# Laser_Tanks_Tank_Motherboard.net
KiCad netlist of a schematic drawn in EasyEDA Pro
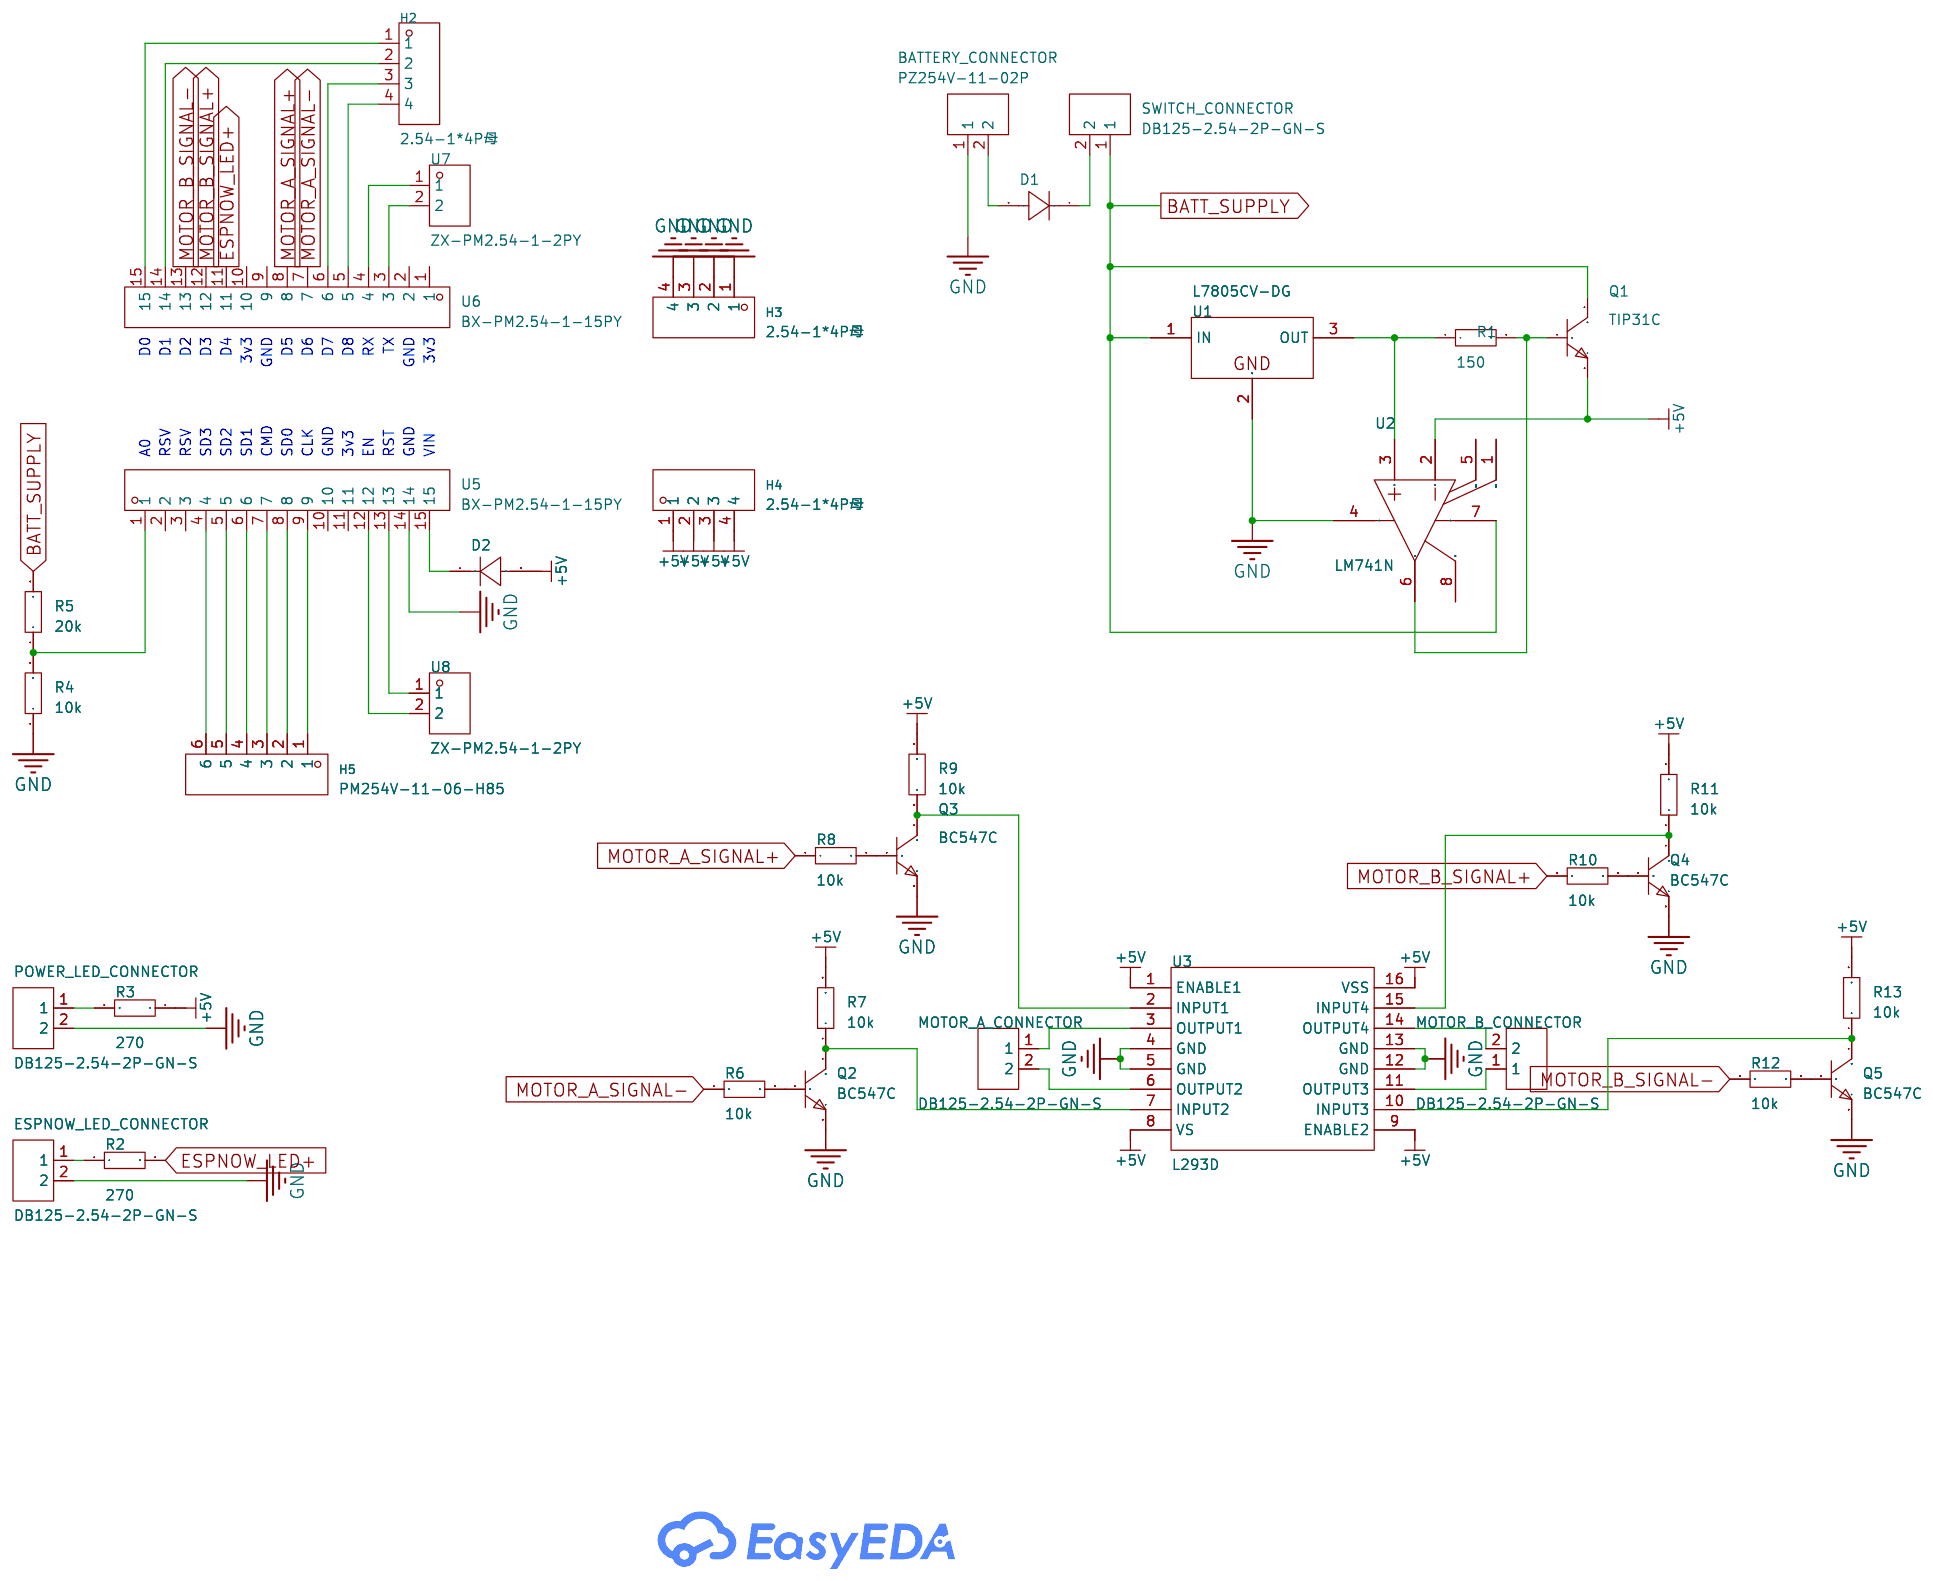
[diagram p0: schematic sheet]

(export (version "E")
  (design (tool "Eeschema 10.0.6"))
  (components
    (comp (ref "BATTERY_CONNECTOR")
      (value "PZ254V-11-02P")
      (footprint "easyedapro:HDR-TH_2P-P2.54-V-M")
      (fields (field (name "Manufacturer") "XFCN(兴飞)"))
      (libsource (lib "easyedapro") (part "PZ254V-11-02P"))
    )
    (comp (ref "D1")
      (value "~")
      (footprint "easyedapro:DO-41_BD2.4-L4.7-P8.70-D0.9-RD")
      (libsource (lib "easyedapro") (part "D_1N4007"))
    )
    (comp (ref "D2")
      (value "~")
      (footprint "easyedapro:DO-41_BD2.4-L4.7-P8.70-D0.9-RD")
      (libsource (lib "easyedapro") (part "D_1N4007"))
    )
    (comp (ref "ESPNOW_LED_CONNECTOR")
      (value "DB125-2.54-2P-GN-S")
      (footprint "easyedapro:CONN-TH_DB125-2.54-2P-GN")
      (fields (field (name "Manufacturer") "DORABO(地博电气)"))
      (libsource (lib "easyedapro") (part "DB125-2.54-2P-GN"))
    )
    (comp (ref "H2")
      (value "2.54-1*4P母")
      (footprint "easyedapro:HDR-TH_4P-P2.54-V-F")
      (fields (field (name "Manufacturer") "BOOMELE(博穆精密)"))
      (libsource (lib "easyedapro") (part "2.54-1*4P母"))
    )
    (comp (ref "H3")
      (value "2.54-1*4P母")
      (footprint "easyedapro:HDR-TH_4P-P2.54-V-F")
      (fields (field (name "Manufacturer") "BOOMELE(博穆精密)"))
      (libsource (lib "easyedapro") (part "2.54-1*4P母"))
    )
    (comp (ref "H4")
      (value "2.54-1*4P母")
      (footprint "easyedapro:HDR-TH_4P-P2.54-V-F")
      (fields (field (name "Manufacturer") "BOOMELE(博穆精密)"))
      (libsource (lib "easyedapro") (part "2.54-1*4P母"))
    )
    (comp (ref "H5")
      (value "PM254V-11-06-H85")
      (footprint "easyedapro:HDR-TH_6P-P2.54-V-F")
      (fields (field (name "Manufacturer") "XFCN(兴飞)"))
      (libsource (lib "easyedapro") (part "PM254V-11-06-H85"))
    )
    (comp (ref "MOTOR_A_CONNECTOR")
      (value "DB125-2.54-2P-GN-S")
      (footprint "easyedapro:CONN-TH_DB125-2.54-2P-GN")
      (fields (field (name "Manufacturer") "DORABO(地博电气)"))
      (libsource (lib "easyedapro") (part "DB125-2.54-2P-GN"))
    )
    (comp (ref "MOTOR_B_CONNECTOR")
      (value "DB125-2.54-2P-GN-S")
      (footprint "easyedapro:CONN-TH_DB125-2.54-2P-GN")
      (fields (field (name "Manufacturer") "DORABO(地博电气)"))
      (libsource (lib "easyedapro") (part "DB125-2.54-2P-GN"))
    )
    (comp (ref "POWER_LED_CONNECTOR")
      (value "DB125-2.54-2P-GN-S")
      (footprint "easyedapro:CONN-TH_DB125-2.54-2P-GN")
      (fields (field (name "Manufacturer") "DORABO(地博电气)"))
      (libsource (lib "easyedapro") (part "DB125-2.54-2P-GN"))
    )
    (comp (ref "Q1")
      (value "TIP31C")
      (footprint "easyedapro:TO-220-3_L10.0-W4.5-P2.54-T")
      (fields (field (name "Manufacturer") "ST(意法半导体)"))
      (libsource (lib "easyedapro") (part "TIP31C"))
    )
    (comp (ref "Q2")
      (value "BC547C")
      (footprint "easyedapro:TO-92-3_L4.9-W3.7-P1.27-L")
      (fields (field (name "Manufacturer") "LGE(鲁光)"))
      (libsource (lib "easyedapro") (part "BC547C"))
    )
    (comp (ref "Q3")
      (value "BC547C")
      (footprint "easyedapro:TO-92-3_L4.9-W3.7-P1.27-L")
      (fields (field (name "Manufacturer") "LGE(鲁光)"))
      (libsource (lib "easyedapro") (part "BC547C"))
    )
    (comp (ref "Q4")
      (value "BC547C")
      (footprint "easyedapro:TO-92-3_L4.9-W3.7-P1.27-L")
      (fields (field (name "Manufacturer") "LGE(鲁光)"))
      (libsource (lib "easyedapro") (part "BC547C"))
    )
    (comp (ref "Q5")
      (value "BC547C")
      (footprint "easyedapro:TO-92-3_L4.9-W3.7-P1.27-L")
      (fields (field (name "Manufacturer") "LGE(鲁光)"))
      (libsource (lib "easyedapro") (part "BC547C"))
    )
    (comp (ref "R1")
      (value "150")
      (footprint "easyedapro:R0603")
      (fields
        (field (name "Manufacturer Part") "MF1/4W-4.7KΩ±1% T")
        (field (name "Manufacturer") "CCO(千志电子)")
      )
      (libsource (lib "easyedapro") (part "Res"))
    )
    (comp (ref "R2")
      (value "270")
      (footprint "easyedapro:R0603")
      (fields
        (field (name "Manufacturer Part") "MF1/4W-4.7KΩ±1% T")
        (field (name "Manufacturer") "CCO(千志电子)")
      )
      (libsource (lib "easyedapro") (part "Res"))
    )
    (comp (ref "R3")
      (value "270")
      (footprint "easyedapro:R0603")
      (fields
        (field (name "Manufacturer Part") "MF1/4W-4.7KΩ±1% T")
        (field (name "Manufacturer") "CCO(千志电子)")
      )
      (libsource (lib "easyedapro") (part "Res"))
    )
    (comp (ref "R4")
      (value "10k")
      (footprint "easyedapro:R0603")
      (fields
        (field (name "Manufacturer Part") "MF1/4W-4.7KΩ±1% T")
        (field (name "Manufacturer") "CCO(千志电子)")
      )
      (libsource (lib "easyedapro") (part "Res"))
    )
    (comp (ref "R5")
      (value "20k")
      (footprint "easyedapro:R0603")
      (fields
        (field (name "Manufacturer Part") "MF1/4W-4.7KΩ±1% T")
        (field (name "Manufacturer") "CCO(千志电子)")
      )
      (libsource (lib "easyedapro") (part "Res"))
    )
    (comp (ref "R6")
      (value "10k")
      (footprint "easyedapro:R0603")
      (fields
        (field (name "Manufacturer Part") "MF1/4W-4.7KΩ±1% T")
        (field (name "Manufacturer") "CCO(千志电子)")
      )
      (libsource (lib "easyedapro") (part "Res"))
    )
    (comp (ref "R7")
      (value "10k")
      (footprint "easyedapro:R0603")
      (fields
        (field (name "Manufacturer Part") "MF1/4W-4.7KΩ±1% T")
        (field (name "Manufacturer") "CCO(千志电子)")
      )
      (libsource (lib "easyedapro") (part "Res"))
    )
    (comp (ref "R8")
      (value "10k")
      (footprint "easyedapro:R0603")
      (fields
        (field (name "Manufacturer Part") "MF1/4W-4.7KΩ±1% T")
        (field (name "Manufacturer") "CCO(千志电子)")
      )
      (libsource (lib "easyedapro") (part "Res"))
    )
    (comp (ref "R9")
      (value "10k")
      (footprint "easyedapro:R0603")
      (fields
        (field (name "Manufacturer Part") "MF1/4W-4.7KΩ±1% T")
        (field (name "Manufacturer") "CCO(千志电子)")
      )
      (libsource (lib "easyedapro") (part "Res"))
    )
    (comp (ref "R10")
      (value "10k")
      (footprint "easyedapro:R0603")
      (fields
        (field (name "Manufacturer Part") "MF1/4W-4.7KΩ±1% T")
        (field (name "Manufacturer") "CCO(千志电子)")
      )
      (libsource (lib "easyedapro") (part "Res"))
    )
    (comp (ref "R11")
      (value "10k")
      (footprint "easyedapro:R0603")
      (fields
        (field (name "Manufacturer Part") "MF1/4W-4.7KΩ±1% T")
        (field (name "Manufacturer") "CCO(千志电子)")
      )
      (libsource (lib "easyedapro") (part "Res"))
    )
    (comp (ref "R12")
      (value "10k")
      (footprint "easyedapro:R0603")
      (fields
        (field (name "Manufacturer Part") "MF1/4W-4.7KΩ±1% T")
        (field (name "Manufacturer") "CCO(千志电子)")
      )
      (libsource (lib "easyedapro") (part "Res"))
    )
    (comp (ref "R13")
      (value "10k")
      (footprint "easyedapro:R0603")
      (fields
        (field (name "Manufacturer Part") "MF1/4W-4.7KΩ±1% T")
        (field (name "Manufacturer") "CCO(千志电子)")
      )
      (libsource (lib "easyedapro") (part "Res"))
    )
    (comp (ref "SWITCH_CONNECTOR")
      (value "DB125-2.54-2P-GN-S")
      (footprint "easyedapro:CONN-TH_DB125-2.54-2P-GN")
      (fields (field (name "Manufacturer") "DORABO(地博电气)"))
      (libsource (lib "easyedapro") (part "DB125-2.54-2P-GN"))
    )
    (comp (ref "U1")
      (value "L7805CV-DG")
      (footprint "easyedapro:TO-220-3_L10.0-W4.5-P2.54-L")
      (fields (field (name "Manufacturer") "ST(意法半导体)"))
      (libsource (lib "easyedapro") (part "L7805CV-DG"))
    )
    (comp (ref "U2")
      (value "LM741N")
      (footprint "easyedapro:DIP-8_L9.3-W6.4-P2.54-LS7.6-BL")
      (fields (field (name "Manufacturer") "HGSEMI(华冠)"))
      (libsource (lib "easyedapro") (part "LM741N"))
    )
    (comp (ref "U3")
      (value "L293D")
      (footprint "easyedapro:DIP-16_L20.0-W6.4-P2.54-LS7.6-BL")
      (fields (field (name "Manufacturer") "ST(意法半导体)"))
      (libsource (lib "easyedapro") (part "L293D"))
    )
    (comp (ref "U5")
      (value "BX-PM2.54-1-15PY")
      (footprint "easyedapro:HDR-TH_15P-P2.54-V-F-1")
      (fields (field (name "Manufacturer") "Bossie(博锡)"))
      (libsource (lib "easyedapro") (part "BX-PM2.54-1-15PY"))
    )
    (comp (ref "U6")
      (value "BX-PM2.54-1-15PY")
      (footprint "easyedapro:HDR-TH_15P-P2.54-V-F-1")
      (fields (field (name "Manufacturer") "Bossie(博锡)"))
      (libsource (lib "easyedapro") (part "BX-PM2.54-1-15PY"))
    )
    (comp (ref "U7")
      (value "ZX-PM2.54-1-2PY")
      (footprint "easyedapro:HDR-TH_2P-P2.54-V-F")
      (fields (field (name "Manufacturer") "Megastar(兆星)"))
      (libsource (lib "easyedapro") (part "ZX-PM2.54-1-2PY"))
    )
    (comp (ref "U8")
      (value "ZX-PM2.54-1-2PY")
      (footprint "easyedapro:HDR-TH_2P-P2.54-V-F")
      (fields (field (name "Manufacturer") "Megastar(兆星)"))
      (libsource (lib "easyedapro") (part "ZX-PM2.54-1-2PY"))
    )
  )
  (nets
    (net (code "1") (name "+5V") (class "Default")
      (node (ref "D2") (pin "2") (pinfunction "A_2") (pintype "input"))
      (node (ref "H4") (pin "1") (pinfunction "1_1") (pintype "input"))
      (node (ref "H4") (pin "2") (pinfunction "2_2") (pintype "input"))
      (node (ref "H4") (pin "3") (pinfunction "3_3") (pintype "input"))
      (node (ref "H4") (pin "4") (pinfunction "4_4") (pintype "input"))
      (node (ref "Q1") (pin "3") (pinfunction "E_3") (pintype "unspecified"))
      (node (ref "R11") (pin "2") (pinfunction "2_2") (pintype "input"))
      (node (ref "R13") (pin "2") (pinfunction "2_2") (pintype "input"))
      (node (ref "R3") (pin "1") (pinfunction "1_1") (pintype "input"))
      (node (ref "R7") (pin "2") (pinfunction "2_2") (pintype "input"))
      (node (ref "R9") (pin "2") (pinfunction "2_2") (pintype "input"))
      (node (ref "U2") (pin "2") (pinfunction "-IN_2") (pintype "unspecified"))
      (node (ref "U3") (pin "1") (pinfunction "ENABLE1_1") (pintype "unspecified"))
      (node (ref "U3") (pin "16") (pinfunction "VSS_16") (pintype "unspecified"))
      (node (ref "U3") (pin "8") (pinfunction "VS_8") (pintype "unspecified"))
      (node (ref "U3") (pin "9") (pinfunction "ENABLE2_9") (pintype "unspecified"))
    )
    (net (code "2") (name "BATT_SUPPLY") (class "Default")
      (node (ref "Q1") (pin "2") (pinfunction "C_2") (pintype "unspecified"))
      (node (ref "R5") (pin "2") (pinfunction "2_2") (pintype "input"))
      (node (ref "SWITCH_CONNECTOR") (pin "1") (pinfunction "1_1") (pintype "unspecified"))
      (node (ref "U1") (pin "1") (pinfunction "IN_1") (pintype "unspecified"))
      (node (ref "U2") (pin "7") (pinfunction "V+_7") (pintype "unspecified"))
    )
    (net (code "3") (name "ESPNOW_LED+") (class "Default")
      (node (ref "R2") (pin "2") (pinfunction "2_2") (pintype "input"))
      (node (ref "U6") (pin "11") (pinfunction "11_11") (pintype "unspecified"))
    )
    (net (code "4") (name "GND") (class "Default")
      (node (ref "BATTERY_CONNECTOR") (pin "1") (pinfunction "1_1") (pintype "unspecified"))
      (node (ref "ESPNOW_LED_CONNECTOR") (pin "2") (pinfunction "2_2") (pintype "unspecified"))
      (node (ref "H3") (pin "1") (pinfunction "1_1") (pintype "input"))
      (node (ref "H3") (pin "2") (pinfunction "2_2") (pintype "input"))
      (node (ref "H3") (pin "3") (pinfunction "3_3") (pintype "input"))
      (node (ref "H3") (pin "4") (pinfunction "4_4") (pintype "input"))
      (node (ref "POWER_LED_CONNECTOR") (pin "2") (pinfunction "2_2") (pintype "unspecified"))
      (node (ref "Q2") (pin "3") (pinfunction "E_3") (pintype "input"))
      (node (ref "Q3") (pin "3") (pinfunction "E_3") (pintype "input"))
      (node (ref "Q4") (pin "3") (pinfunction "E_3") (pintype "input"))
      (node (ref "Q5") (pin "3") (pinfunction "E_3") (pintype "input"))
      (node (ref "R4") (pin "1") (pinfunction "1_1") (pintype "input"))
      (node (ref "U1") (pin "2") (pinfunction "GND_2") (pintype "unspecified"))
      (node (ref "U2") (pin "4") (pinfunction "V-_4") (pintype "unspecified"))
      (node (ref "U3") (pin "12") (pinfunction "GND_12") (pintype "unspecified"))
      (node (ref "U3") (pin "13") (pinfunction "GND_13") (pintype "unspecified"))
      (node (ref "U3") (pin "4") (pinfunction "GND_4") (pintype "unspecified"))
      (node (ref "U3") (pin "5") (pinfunction "GND_5") (pintype "unspecified"))
      (node (ref "U5") (pin "14") (pinfunction "14_14") (pintype "unspecified"))
    )
    (net (code "5") (name "MOTOR_A_SIGNAL+") (class "Default")
      (node (ref "R8") (pin "1") (pinfunction "1_1") (pintype "input"))
      (node (ref "U6") (pin "8") (pinfunction "8_8") (pintype "unspecified"))
    )
    (net (code "6") (name "MOTOR_A_SIGNAL-") (class "Default")
      (node (ref "R6") (pin "1") (pinfunction "1_1") (pintype "input"))
      (node (ref "U6") (pin "7") (pinfunction "7_7") (pintype "unspecified"))
    )
    (net (code "7") (name "MOTOR_B_SIGNAL+") (class "Default")
      (node (ref "R10") (pin "1") (pinfunction "1_1") (pintype "input"))
      (node (ref "U6") (pin "12") (pinfunction "12_12") (pintype "unspecified"))
    )
    (net (code "8") (name "MOTOR_B_SIGNAL-") (class "Default")
      (node (ref "R12") (pin "1") (pinfunction "1_1") (pintype "input"))
      (node (ref "U6") (pin "13") (pinfunction "13_13") (pintype "unspecified"))
    )
    (net (code "9") (name "Net-(D1-A)") (class "Default")
      (node (ref "BATTERY_CONNECTOR") (pin "2") (pinfunction "2_2") (pintype "unspecified"))
      (node (ref "D1") (pin "2") (pinfunction "A_2") (pintype "input"))
    )
    (net (code "10") (name "Net-(D1-K)") (class "Default")
      (node (ref "D1") (pin "1") (pinfunction "K_1") (pintype "input"))
      (node (ref "SWITCH_CONNECTOR") (pin "2") (pinfunction "2_2") (pintype "unspecified"))
    )
    (net (code "11") (name "Net-(D2-K)") (class "Default")
      (node (ref "D2") (pin "1") (pinfunction "K_1") (pintype "input"))
      (node (ref "U5") (pin "15") (pinfunction "15_15") (pintype "unspecified"))
    )
    (net (code "12") (name "Net-(ESPNOW_LED_CONNECTOR-Pad1)") (class "Default")
      (node (ref "ESPNOW_LED_CONNECTOR") (pin "1") (pinfunction "1_1") (pintype "unspecified"))
      (node (ref "R2") (pin "1") (pinfunction "1_1") (pintype "input"))
    )
    (net (code "13") (name "Net-(H2-Pad1)") (class "Default")
      (node (ref "H2") (pin "1") (pinfunction "1_1") (pintype "input"))
      (node (ref "U6") (pin "15") (pinfunction "15_15") (pintype "unspecified"))
    )
    (net (code "14") (name "Net-(H2-Pad2)") (class "Default")
      (node (ref "H2") (pin "2") (pinfunction "2_2") (pintype "input"))
      (node (ref "U6") (pin "14") (pinfunction "14_14") (pintype "unspecified"))
    )
    (net (code "15") (name "Net-(H2-Pad3)") (class "Default")
      (node (ref "H2") (pin "3") (pinfunction "3_3") (pintype "input"))
      (node (ref "U6") (pin "6") (pinfunction "6_6") (pintype "unspecified"))
    )
    (net (code "16") (name "Net-(H2-Pad4)") (class "Default")
      (node (ref "H2") (pin "4") (pinfunction "4_4") (pintype "input"))
      (node (ref "U6") (pin "5") (pinfunction "5_5") (pintype "unspecified"))
    )
    (net (code "17") (name "Net-(H5-Pad1)") (class "Default")
      (node (ref "H5") (pin "1") (pinfunction "1_1") (pintype "input"))
      (node (ref "U5") (pin "9") (pinfunction "9_9") (pintype "unspecified"))
    )
    (net (code "18") (name "Net-(H5-Pad2)") (class "Default")
      (node (ref "H5") (pin "2") (pinfunction "2_2") (pintype "input"))
      (node (ref "U5") (pin "8") (pinfunction "8_8") (pintype "unspecified"))
    )
    (net (code "19") (name "Net-(H5-Pad3)") (class "Default")
      (node (ref "H5") (pin "3") (pinfunction "3_3") (pintype "input"))
      (node (ref "U5") (pin "7") (pinfunction "7_7") (pintype "unspecified"))
    )
    (net (code "20") (name "Net-(H5-Pad4)") (class "Default")
      (node (ref "H5") (pin "4") (pinfunction "4_4") (pintype "input"))
      (node (ref "U5") (pin "6") (pinfunction "6_6") (pintype "unspecified"))
    )
    (net (code "21") (name "Net-(H5-Pad5)") (class "Default")
      (node (ref "H5") (pin "5") (pinfunction "5_5") (pintype "input"))
      (node (ref "U5") (pin "5") (pinfunction "5_5") (pintype "unspecified"))
    )
    (net (code "22") (name "Net-(H5-Pad6)") (class "Default")
      (node (ref "H5") (pin "6") (pinfunction "6_6") (pintype "input"))
      (node (ref "U5") (pin "4") (pinfunction "4_4") (pintype "unspecified"))
    )
    (net (code "23") (name "Net-(POWER_LED_CONNECTOR-Pad1)") (class "Default")
      (node (ref "POWER_LED_CONNECTOR") (pin "1") (pinfunction "1_1") (pintype "unspecified"))
      (node (ref "R3") (pin "2") (pinfunction "2_2") (pintype "input"))
    )
    (net (code "24") (name "Net-(Q1-B)") (class "Default")
      (node (ref "Q1") (pin "1") (pinfunction "B_1") (pintype "unspecified"))
      (node (ref "R1") (pin "2") (pinfunction "2_2") (pintype "input"))
      (node (ref "U2") (pin "6") (pinfunction "OUT_6") (pintype "output"))
    )
    (net (code "25") (name "Net-(Q2-B)") (class "Default")
      (node (ref "Q2") (pin "2") (pinfunction "B_2") (pintype "input"))
      (node (ref "R6") (pin "2") (pinfunction "2_2") (pintype "input"))
    )
    (net (code "26") (name "Net-(Q2-C)") (class "Default")
      (node (ref "Q2") (pin "1") (pinfunction "C_1") (pintype "input"))
      (node (ref "R7") (pin "1") (pinfunction "1_1") (pintype "input"))
      (node (ref "U3") (pin "7") (pinfunction "INPUT2_7") (pintype "unspecified"))
    )
    (net (code "27") (name "Net-(Q3-B)") (class "Default")
      (node (ref "Q3") (pin "2") (pinfunction "B_2") (pintype "input"))
      (node (ref "R8") (pin "2") (pinfunction "2_2") (pintype "input"))
    )
    (net (code "28") (name "Net-(Q3-C)") (class "Default")
      (node (ref "Q3") (pin "1") (pinfunction "C_1") (pintype "input"))
      (node (ref "R9") (pin "1") (pinfunction "1_1") (pintype "input"))
      (node (ref "U3") (pin "2") (pinfunction "INPUT1_2") (pintype "unspecified"))
    )
    (net (code "29") (name "Net-(Q4-B)") (class "Default")
      (node (ref "Q4") (pin "2") (pinfunction "B_2") (pintype "input"))
      (node (ref "R10") (pin "2") (pinfunction "2_2") (pintype "input"))
    )
    (net (code "30") (name "Net-(Q4-C)") (class "Default")
      (node (ref "Q4") (pin "1") (pinfunction "C_1") (pintype "input"))
      (node (ref "R11") (pin "1") (pinfunction "1_1") (pintype "input"))
      (node (ref "U3") (pin "15") (pinfunction "INPUT4_15") (pintype "unspecified"))
    )
    (net (code "31") (name "Net-(Q5-B)") (class "Default")
      (node (ref "Q5") (pin "2") (pinfunction "B_2") (pintype "input"))
      (node (ref "R12") (pin "2") (pinfunction "2_2") (pintype "input"))
    )
    (net (code "32") (name "Net-(Q5-C)") (class "Default")
      (node (ref "Q5") (pin "1") (pinfunction "C_1") (pintype "input"))
      (node (ref "R13") (pin "1") (pinfunction "1_1") (pintype "input"))
      (node (ref "U3") (pin "10") (pinfunction "INPUT3_10") (pintype "unspecified"))
    )
    (net (code "33") (name "Net-(R4-Pad2)") (class "Default")
      (node (ref "R4") (pin "2") (pinfunction "2_2") (pintype "input"))
      (node (ref "R5") (pin "1") (pinfunction "1_1") (pintype "input"))
      (node (ref "U5") (pin "1") (pinfunction "1_1") (pintype "unspecified"))
    )
    (net (code "34") (name "Net-(U1-OUT)") (class "Default")
      (node (ref "R1") (pin "1") (pinfunction "1_1") (pintype "input"))
      (node (ref "U1") (pin "3") (pinfunction "OUT_3") (pintype "unspecified"))
      (node (ref "U2") (pin "3") (pinfunction "+IN_3") (pintype "unspecified"))
    )
    (net (code "35") (name "Net-(U3-OUTPUT1)") (class "Default")
      (node (ref "MOTOR_A_CONNECTOR") (pin "1") (pinfunction "1_1") (pintype "unspecified"))
      (node (ref "U3") (pin "3") (pinfunction "OUTPUT1_3") (pintype "unspecified"))
    )
    (net (code "36") (name "Net-(U3-OUTPUT2)") (class "Default")
      (node (ref "MOTOR_A_CONNECTOR") (pin "2") (pinfunction "2_2") (pintype "unspecified"))
      (node (ref "U3") (pin "6") (pinfunction "OUTPUT2_6") (pintype "unspecified"))
    )
    (net (code "37") (name "Net-(U3-OUTPUT3)") (class "Default")
      (node (ref "MOTOR_B_CONNECTOR") (pin "1") (pinfunction "1_1") (pintype "unspecified"))
      (node (ref "U3") (pin "11") (pinfunction "OUTPUT3_11") (pintype "unspecified"))
    )
    (net (code "38") (name "Net-(U3-OUTPUT4)") (class "Default")
      (node (ref "MOTOR_B_CONNECTOR") (pin "2") (pinfunction "2_2") (pintype "unspecified"))
      (node (ref "U3") (pin "14") (pinfunction "OUTPUT4_14") (pintype "unspecified"))
    )
    (net (code "39") (name "Net-(U5-Pad12)") (class "Default")
      (node (ref "U5") (pin "12") (pinfunction "12_12") (pintype "unspecified"))
      (node (ref "U8") (pin "2") (pinfunction "2_2") (pintype "unspecified"))
    )
    (net (code "40") (name "Net-(U5-Pad13)") (class "Default")
      (node (ref "U5") (pin "13") (pinfunction "13_13") (pintype "unspecified"))
      (node (ref "U8") (pin "1") (pinfunction "1_1") (pintype "unspecified"))
    )
    (net (code "41") (name "Net-(U6-Pad3)") (class "Default")
      (node (ref "U6") (pin "3") (pinfunction "3_3") (pintype "unspecified"))
      (node (ref "U7") (pin "2") (pinfunction "2_2") (pintype "unspecified"))
    )
    (net (code "42") (name "Net-(U6-Pad4)") (class "Default")
      (node (ref "U6") (pin "4") (pinfunction "4_4") (pintype "unspecified"))
      (node (ref "U7") (pin "1") (pinfunction "1_1") (pintype "unspecified"))
    )
    (net (code "43") (name "unconnected-(U2-NC-Pad8)") (class "Default")
      (node (ref "U2") (pin "8") (pinfunction "NC_8") (pintype "unspecified"))
    )
    (net (code "44") (name "unconnected-(U2-OFFSET_NULL-Pad1)") (class "Default")
      (node (ref "U2") (pin "1") (pinfunction "OFFSET_NULL_1") (pintype "unspecified"))
    )
    (net (code "45") (name "unconnected-(U2-OFFSET_NULL-Pad5)") (class "Default")
      (node (ref "U2") (pin "5") (pinfunction "OFFSET_NULL_5") (pintype "unspecified"))
    )
    (net (code "46") (name "unconnected-(U5-Pad2)") (class "Default")
      (node (ref "U5") (pin "2") (pinfunction "2_2") (pintype "unspecified"))
    )
    (net (code "47") (name "unconnected-(U5-Pad3)") (class "Default")
      (node (ref "U5") (pin "3") (pinfunction "3_3") (pintype "unspecified"))
    )
    (net (code "48") (name "unconnected-(U5-Pad10)") (class "Default")
      (node (ref "U5") (pin "10") (pinfunction "10_10") (pintype "unspecified"))
    )
    (net (code "49") (name "unconnected-(U5-Pad11)") (class "Default")
      (node (ref "U5") (pin "11") (pinfunction "11_11") (pintype "unspecified"))
    )
    (net (code "50") (name "unconnected-(U6-Pad1)") (class "Default")
      (node (ref "U6") (pin "1") (pinfunction "1_1") (pintype "unspecified"))
    )
    (net (code "51") (name "unconnected-(U6-Pad2)") (class "Default")
      (node (ref "U6") (pin "2") (pinfunction "2_2") (pintype "unspecified"))
    )
    (net (code "52") (name "unconnected-(U6-Pad9)") (class "Default")
      (node (ref "U6") (pin "9") (pinfunction "9_9") (pintype "unspecified"))
    )
    (net (code "53") (name "unconnected-(U6-Pad10)") (class "Default")
      (node (ref "U6") (pin "10") (pinfunction "10_10") (pintype "unspecified"))
    )
  )
)
